# hexapod_mk2_leg_v0_0.net
KiCad netlist of a schematic drawn in EAGLE
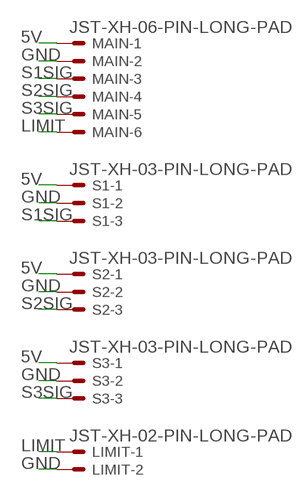
[diagram p0: schematic, sheet 1]

(export (version "E")
  (design (tool "Eeschema 10.0.6"))
  (components
    (comp (ref "LIMIT")
      (value "JST-XH-02-PIN-LONG-PAD")
      (footprint "eagle-import:JST-XH-02-PACKAGE-LONG-PAD")
      (libsource (lib "eagle-import") (part "JST-XH-02-PIN-LONG-PAD"))
    )
    (comp (ref "MAIN")
      (value "JST-XH-06-PIN-LONG-PAD")
      (footprint "eagle-import:JST-XH-06-PACKAGE-LONG-PAD")
      (libsource (lib "eagle-import") (part "JST-XH-06-PIN-LONG-PAD"))
    )
    (comp (ref "S1")
      (value "JST-XH-03-PIN-LONG-PAD")
      (footprint "eagle-import:JST-XH-03-PACKAGE-LONG-PAD")
      (libsource (lib "eagle-import") (part "JST-XH-03-PIN-LONG-PAD"))
    )
    (comp (ref "S2")
      (value "JST-XH-03-PIN-LONG-PAD")
      (footprint "eagle-import:JST-XH-03-PACKAGE-LONG-PAD")
      (libsource (lib "eagle-import") (part "JST-XH-03-PIN-LONG-PAD"))
    )
    (comp (ref "S3")
      (value "JST-XH-03-PIN-LONG-PAD")
      (footprint "eagle-import:JST-XH-03-PACKAGE-LONG-PAD")
      (libsource (lib "eagle-import") (part "JST-XH-03-PIN-LONG-PAD"))
    )
  )
  (nets
    (net (code "1") (name "/5V") (class "Default")
      (node (ref "MAIN") (pin "1") (pinfunction "S_1") (pintype "passive"))
      (node (ref "S1") (pin "1") (pinfunction "S_1") (pintype "passive"))
      (node (ref "S2") (pin "1") (pinfunction "S_1") (pintype "passive"))
      (node (ref "S3") (pin "1") (pinfunction "S_1") (pintype "passive"))
    )
    (net (code "2") (name "/GND") (class "Default")
      (node (ref "LIMIT") (pin "2") (pinfunction "S_2") (pintype "passive"))
      (node (ref "MAIN") (pin "2") (pinfunction "S_2") (pintype "passive"))
      (node (ref "S1") (pin "2") (pinfunction "S_2") (pintype "passive"))
      (node (ref "S2") (pin "2") (pinfunction "S_2") (pintype "passive"))
      (node (ref "S3") (pin "2") (pinfunction "S_2") (pintype "passive"))
    )
    (net (code "3") (name "/LIMIT") (class "Default")
      (node (ref "LIMIT") (pin "1") (pinfunction "S_1") (pintype "passive"))
      (node (ref "MAIN") (pin "6") (pinfunction "S_6") (pintype "passive"))
    )
    (net (code "4") (name "/S1SIG") (class "Default")
      (node (ref "MAIN") (pin "3") (pinfunction "S_3") (pintype "passive"))
      (node (ref "S1") (pin "3") (pinfunction "S_3") (pintype "passive"))
    )
    (net (code "5") (name "/S2SIG") (class "Default")
      (node (ref "MAIN") (pin "4") (pinfunction "S_4") (pintype "passive"))
      (node (ref "S2") (pin "3") (pinfunction "S_3") (pintype "passive"))
    )
    (net (code "6") (name "/S3SIG") (class "Default")
      (node (ref "MAIN") (pin "5") (pinfunction "S_5") (pintype "passive"))
      (node (ref "S3") (pin "3") (pinfunction "S_3") (pintype "passive"))
    )
  )
)
